# solderpeek.net
KiCad netlist of a schematic drawn in EAGLE
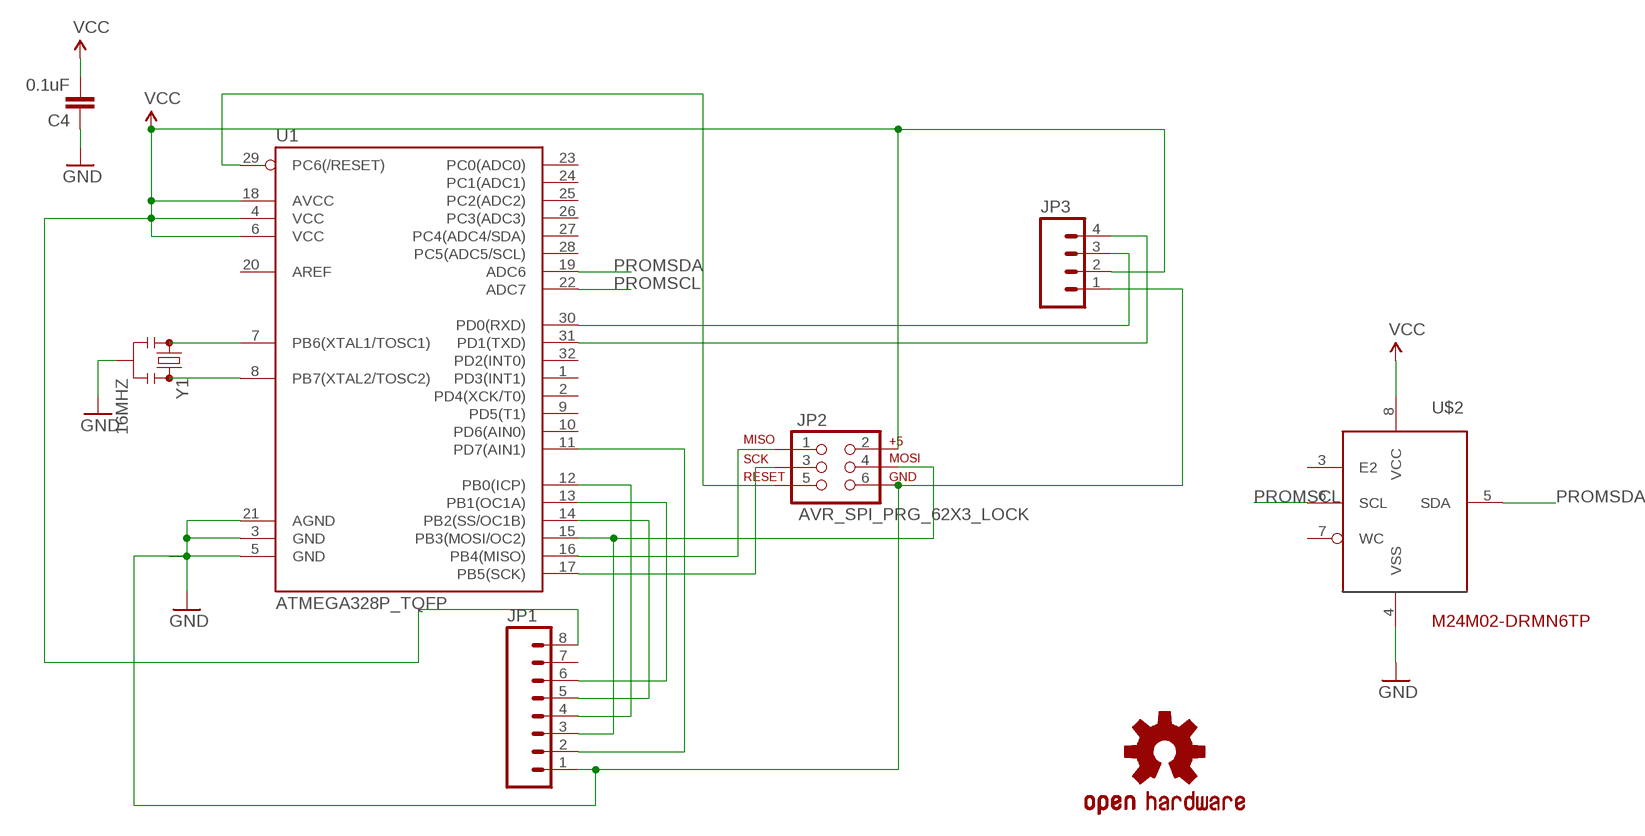
[diagram p0: schematic, sheet 1]

(export (version "E")
  (design (tool "Eeschema 10.0.6"))
  (components
    (comp (ref "C4")
      (value "0.1uF")
      (footprint "eagle-import:0603-CAP")
      (libsource (lib "eagle-import") (part "0.1UF-25V(+80/-20%)(0603)"))
    )
    (comp (ref "JP1")
      (value "M08LOCK")
      (footprint "eagle-import:1X08_LOCK")
      (libsource (lib "eagle-import") (part "M08LOCK"))
    )
    (comp (ref "JP2")
      (value "AVR_SPI_PRG_62X3_LOCK")
      (footprint "eagle-import:2X3_LOCK")
      (libsource (lib "eagle-import") (part "AVR_SPI_PRG_62X3_LOCK"))
    )
    (comp (ref "JP3")
      (value "M04LOCK")
      (footprint "eagle-import:1X04_LOCK")
      (libsource (lib "eagle-import") (part "M04LOCK"))
    )
    (comp (ref "LOGO1")
      (value "OSHW-LOGOS")
      (footprint "eagle-import:OSHW-LOGO-S")
      (libsource (lib "eagle-import") (part "OSHW-LOGOS"))
    )
    (comp (ref "U$2")
      (value "M24M02-DRMN6TP")
      (footprint "eagle-import:SO8")
      (libsource (lib "eagle-import") (part "M24M02-DRMN6TP"))
    )
    (comp (ref "U1")
      (value "ATMEGA328P_TQFP")
      (footprint "eagle-import:TQFP32-08")
      (libsource (lib "eagle-import") (part "ATMEGA328P_TQFP"))
    )
    (comp (ref "Y1")
      (value "16MHZ")
      (footprint "eagle-import:RESONATOR-SMD")
      (libsource (lib "eagle-import") (part "RESONATOR16MHZ"))
    )
  )
  (nets
    (net (code "1") (name "/PROMSCL") (class "Default")
      (node (ref "U$2") (pin "6") (pinfunction "SCL_6") (pintype "bidirectional"))
      (node (ref "U1") (pin "22") (pinfunction "ADC7_22") (pintype "bidirectional"))
    )
    (net (code "2") (name "/PROMSDA") (class "Default")
      (node (ref "U$2") (pin "5") (pinfunction "SDA_5") (pintype "bidirectional"))
      (node (ref "U1") (pin "19") (pinfunction "ADC6_19") (pintype "bidirectional"))
    )
    (net (code "3") (name "GND") (class "Default")
      (node (ref "C4") (pin "1") (pinfunction "1_1") (pintype "passive"))
      (node (ref "JP1") (pin "1") (pinfunction "1_1") (pintype "passive"))
      (node (ref "JP2") (pin "6") (pinfunction "6_6") (pintype "passive"))
      (node (ref "JP3") (pin "1") (pinfunction "1_1") (pintype "passive"))
      (node (ref "U$2") (pin "4") (pinfunction "VSS_4") (pintype "power_in"))
      (node (ref "U1") (pin "21") (pinfunction "AGND_21") (pintype "bidirectional"))
      (node (ref "U1") (pin "3") (pinfunction "GND_3") (pintype "bidirectional"))
      (node (ref "U1") (pin "5") (pinfunction "GND_5") (pintype "bidirectional"))
      (node (ref "Y1") (pin "2") (pinfunction "2_2") (pintype "passive"))
    )
    (net (code "4") (name "Net-(U1-PB0(ICP))") (class "Default")
      (node (ref "JP1") (pin "4") (pinfunction "4_4") (pintype "passive"))
      (node (ref "U1") (pin "12") (pinfunction "PB0(ICP)_12") (pintype "bidirectional"))
    )
    (net (code "5") (name "Net-(U1-PB1(OC1A))") (class "Default")
      (node (ref "JP1") (pin "6") (pinfunction "6_6") (pintype "passive"))
      (node (ref "U1") (pin "13") (pinfunction "PB1(OC1A)_13") (pintype "bidirectional"))
    )
    (net (code "6") (name "Net-(U1-PB2(SS{slash}OC1B))") (class "Default")
      (node (ref "JP1") (pin "5") (pinfunction "5_5") (pintype "passive"))
      (node (ref "U1") (pin "14") (pinfunction "PB2(SS/OC1B)_14") (pintype "bidirectional"))
    )
    (net (code "7") (name "Net-(U1-PB3(MOSI{slash}OC2))") (class "Default")
      (node (ref "JP1") (pin "3") (pinfunction "3_3") (pintype "passive"))
      (node (ref "JP2") (pin "4") (pinfunction "4_4") (pintype "passive"))
      (node (ref "U1") (pin "15") (pinfunction "PB3(MOSI/OC2)_15") (pintype "bidirectional"))
    )
    (net (code "8") (name "Net-(U1-PB4(MISO))") (class "Default")
      (node (ref "JP2") (pin "1") (pinfunction "1_1") (pintype "passive"))
      (node (ref "U1") (pin "16") (pinfunction "PB4(MISO)_16") (pintype "bidirectional"))
    )
    (net (code "9") (name "Net-(U1-PB5(SCK))") (class "Default")
      (node (ref "JP2") (pin "3") (pinfunction "3_3") (pintype "passive"))
      (node (ref "U1") (pin "17") (pinfunction "PB5(SCK)_17") (pintype "bidirectional"))
    )
    (net (code "10") (name "Net-(U1-PB6(XTAL1{slash}TOSC1))") (class "Default")
      (node (ref "U1") (pin "7") (pinfunction "PB6(XTAL1/TOSC1)_7") (pintype "bidirectional"))
      (node (ref "Y1") (pin "1") (pinfunction "1_1") (pintype "passive"))
    )
    (net (code "11") (name "Net-(U1-PB7(XTAL2{slash}TOSC2))") (class "Default")
      (node (ref "U1") (pin "8") (pinfunction "PB7(XTAL2/TOSC2)_8") (pintype "bidirectional"))
      (node (ref "Y1") (pin "3") (pinfunction "3_3") (pintype "passive"))
    )
    (net (code "12") (name "Net-(U1-PC6({slash}RESET))") (class "Default")
      (node (ref "JP2") (pin "5") (pinfunction "5_5") (pintype "passive"))
      (node (ref "U1") (pin "29") (pinfunction "PC6(/RESET)_29") (pintype "bidirectional"))
    )
    (net (code "13") (name "Net-(U1-PD0(RXD))") (class "Default")
      (node (ref "JP3") (pin "3") (pinfunction "3_3") (pintype "passive"))
      (node (ref "U1") (pin "30") (pinfunction "PD0(RXD)_30") (pintype "bidirectional"))
    )
    (net (code "14") (name "Net-(U1-PD1(TXD))") (class "Default")
      (node (ref "JP3") (pin "4") (pinfunction "4_4") (pintype "passive"))
      (node (ref "U1") (pin "31") (pinfunction "PD1(TXD)_31") (pintype "bidirectional"))
    )
    (net (code "15") (name "Net-(U1-PD7(AIN1))") (class "Default")
      (node (ref "JP1") (pin "2") (pinfunction "2_2") (pintype "passive"))
      (node (ref "U1") (pin "11") (pinfunction "PD7(AIN1)_11") (pintype "bidirectional"))
    )
    (net (code "16") (name "VCC") (class "Default")
      (node (ref "C4") (pin "2") (pinfunction "2_2") (pintype "passive"))
      (node (ref "JP1") (pin "8") (pinfunction "8_8") (pintype "passive"))
      (node (ref "JP2") (pin "2") (pinfunction "2_2") (pintype "passive"))
      (node (ref "JP3") (pin "2") (pinfunction "2_2") (pintype "passive"))
      (node (ref "U$2") (pin "8") (pinfunction "VCC_8") (pintype "power_in"))
      (node (ref "U1") (pin "18") (pinfunction "AVCC_18") (pintype "bidirectional"))
      (node (ref "U1") (pin "4") (pinfunction "VCC_4") (pintype "bidirectional"))
      (node (ref "U1") (pin "6") (pinfunction "VCC_6") (pintype "bidirectional"))
    )
    (net (code "17") (name "unconnected-(JP1-Pad7)") (class "Default")
      (node (ref "JP1") (pin "7") (pinfunction "7_7") (pintype "passive"))
    )
    (net (code "18") (name "unconnected-(U$2-E2-Pad3)") (class "Default")
      (node (ref "U$2") (pin "3") (pinfunction "E2_3") (pintype "input"))
    )
    (net (code "19") (name "unconnected-(U$2-WC-Pad7)") (class "Default")
      (node (ref "U$2") (pin "7") (pinfunction "WC_7") (pintype "input"))
    )
    (net (code "20") (name "unconnected-(U1-AREF-Pad20)") (class "Default")
      (node (ref "U1") (pin "20") (pinfunction "AREF_20") (pintype "bidirectional"))
    )
    (net (code "21") (name "unconnected-(U1-PC0(ADC0)-Pad23)") (class "Default")
      (node (ref "U1") (pin "23") (pinfunction "PC0(ADC0)_23") (pintype "bidirectional"))
    )
    (net (code "22") (name "unconnected-(U1-PC1(ADC1)-Pad24)") (class "Default")
      (node (ref "U1") (pin "24") (pinfunction "PC1(ADC1)_24") (pintype "bidirectional"))
    )
    (net (code "23") (name "unconnected-(U1-PC2(ADC2)-Pad25)") (class "Default")
      (node (ref "U1") (pin "25") (pinfunction "PC2(ADC2)_25") (pintype "bidirectional"))
    )
    (net (code "24") (name "unconnected-(U1-PC3(ADC3)-Pad26)") (class "Default")
      (node (ref "U1") (pin "26") (pinfunction "PC3(ADC3)_26") (pintype "bidirectional"))
    )
    (net (code "25") (name "unconnected-(U1-PC4(ADC4{slash}SDA)-Pad27)") (class "Default")
      (node (ref "U1") (pin "27") (pinfunction "PC4(ADC4/SDA)_27") (pintype "bidirectional"))
    )
    (net (code "26") (name "unconnected-(U1-PC5(ADC5{slash}SCL)-Pad28)") (class "Default")
      (node (ref "U1") (pin "28") (pinfunction "PC5(ADC5/SCL)_28") (pintype "bidirectional"))
    )
    (net (code "27") (name "unconnected-(U1-PD2(INT0)-Pad32)") (class "Default")
      (node (ref "U1") (pin "32") (pinfunction "PD2(INT0)_32") (pintype "bidirectional"))
    )
    (net (code "28") (name "unconnected-(U1-PD3(INT1)-Pad1)") (class "Default")
      (node (ref "U1") (pin "1") (pinfunction "PD3(INT1)_1") (pintype "bidirectional"))
    )
    (net (code "29") (name "unconnected-(U1-PD4(XCK{slash}T0)-Pad2)") (class "Default")
      (node (ref "U1") (pin "2") (pinfunction "PD4(XCK/T0)_2") (pintype "bidirectional"))
    )
    (net (code "30") (name "unconnected-(U1-PD5(T1)-Pad9)") (class "Default")
      (node (ref "U1") (pin "9") (pinfunction "PD5(T1)_9") (pintype "bidirectional"))
    )
    (net (code "31") (name "unconnected-(U1-PD6(AIN0)-Pad10)") (class "Default")
      (node (ref "U1") (pin "10") (pinfunction "PD6(AIN0)_10") (pintype "bidirectional"))
    )
  )
)
